# Solenoid_Driver_x8.net
KiCad netlist of a schematic drawn in EAGLE
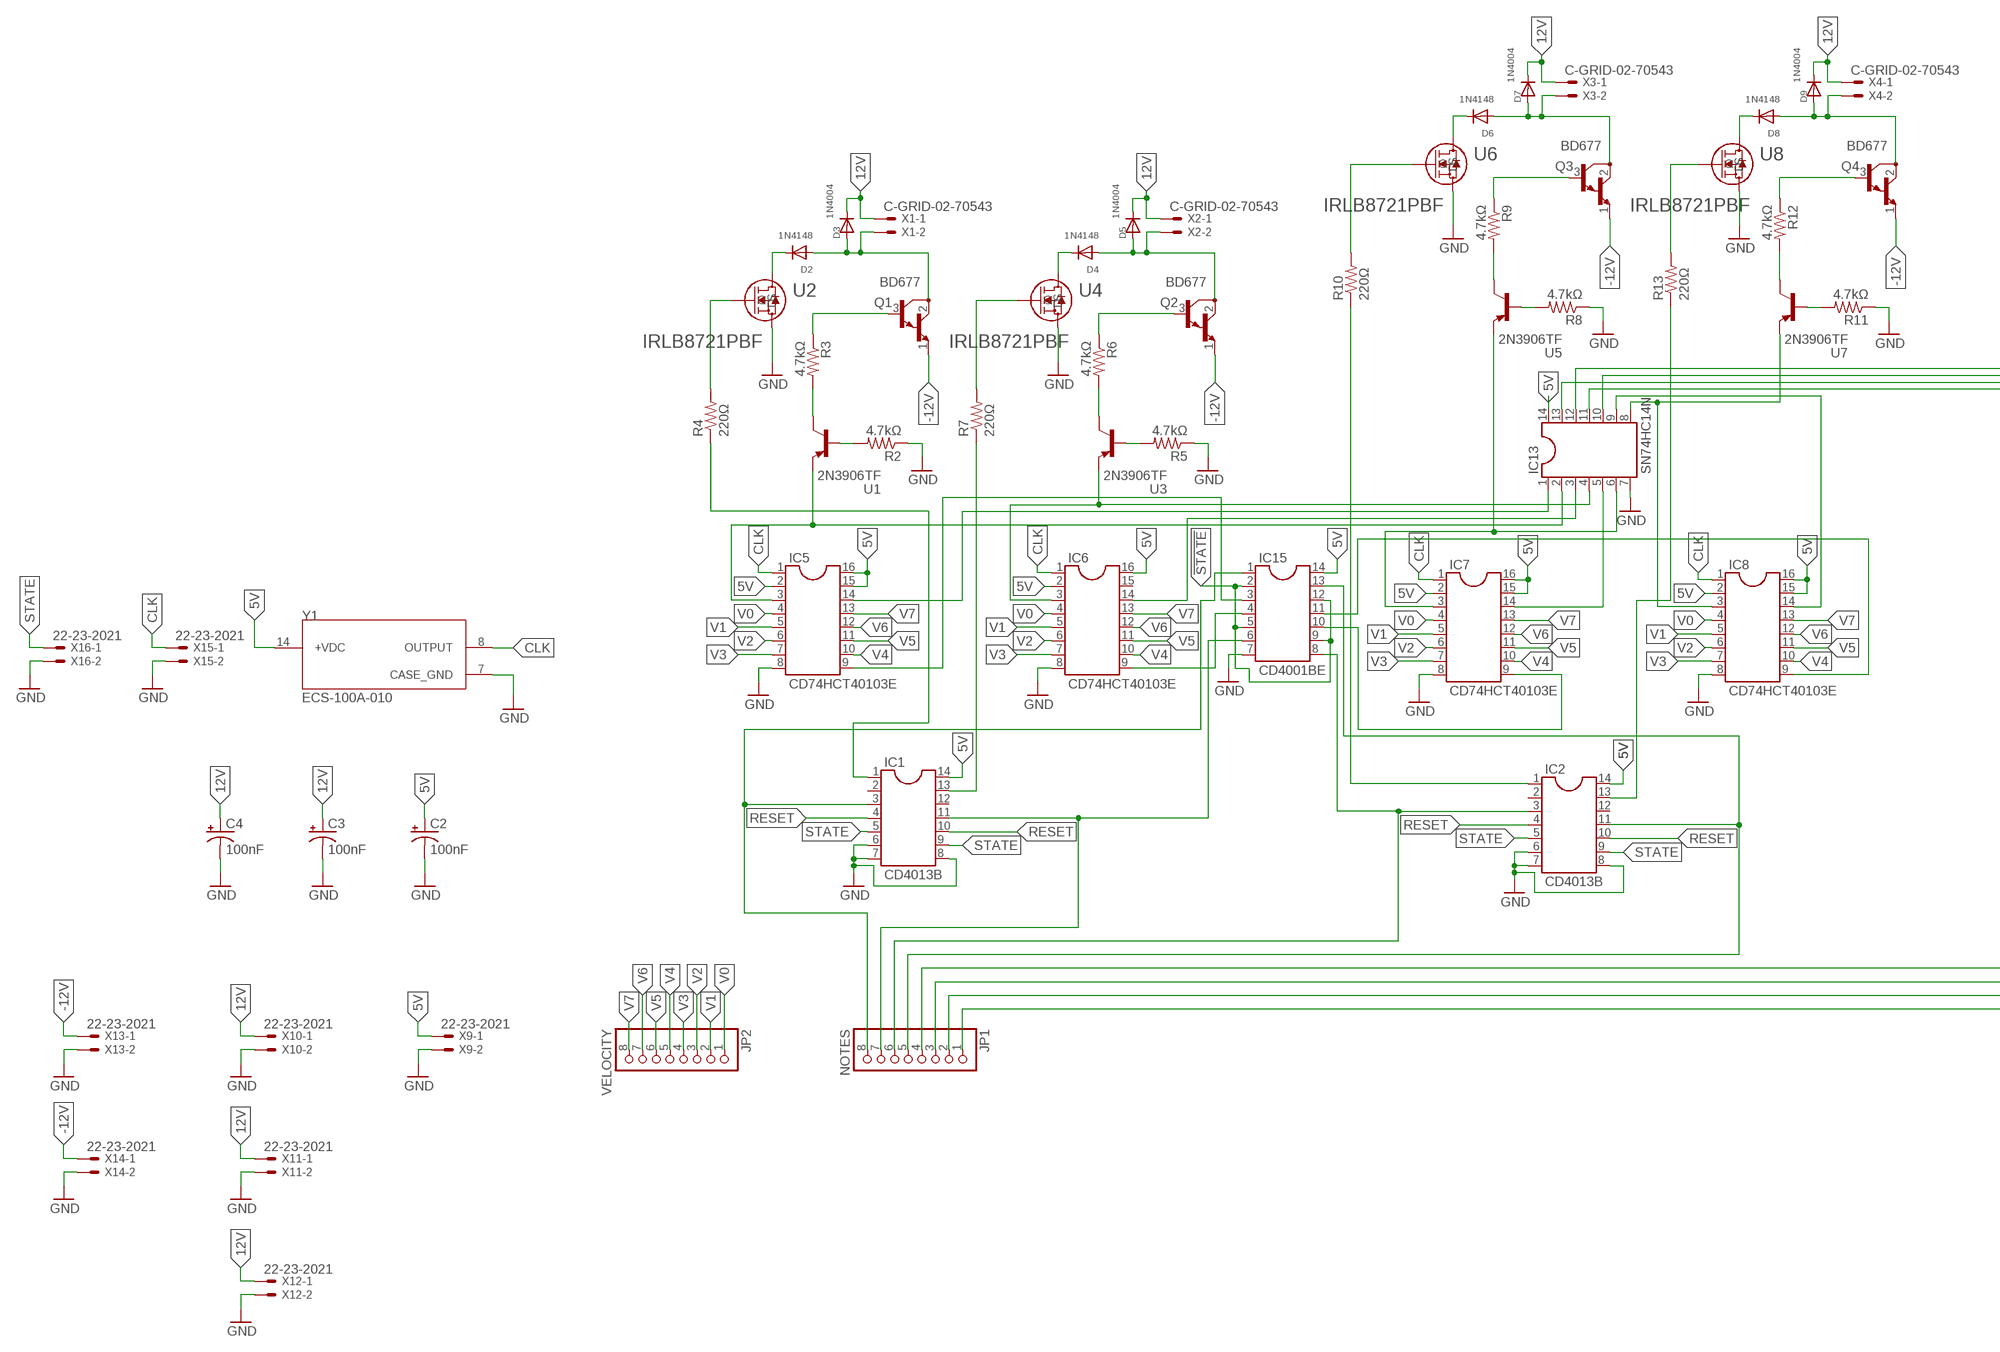
[diagram p0: schematic, sheet 1, part 1 of 2]
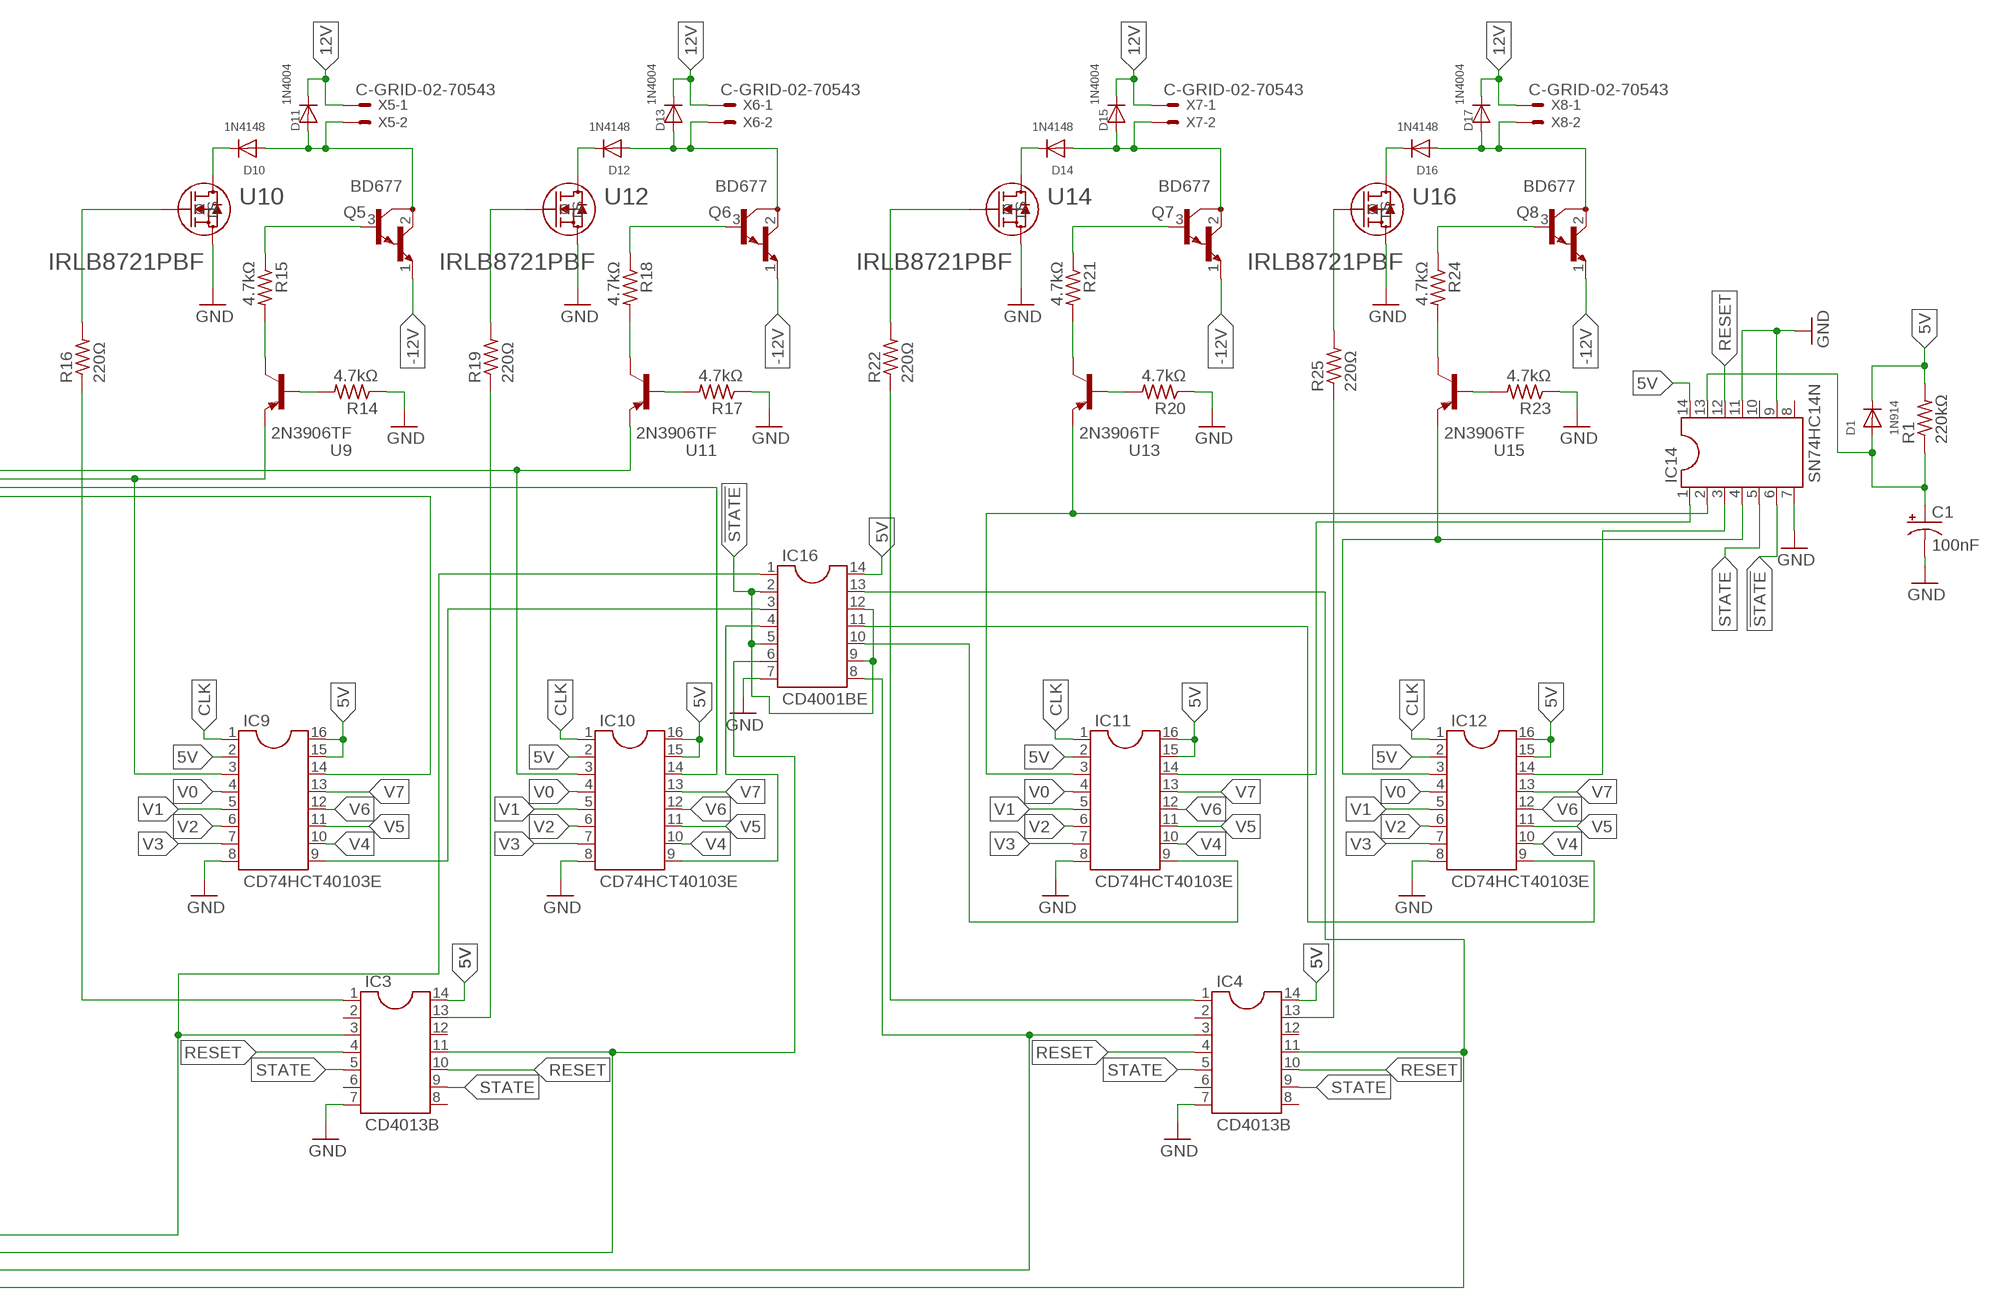
[diagram p1: schematic, sheet 1, part 2 of 2]

(export (version "E")
  (design (tool "Eeschema 10.0.6"))
  (components
    (comp (ref "C1")
      (value "100nF")
      (footprint "eagle-import:E1,8-4")
      (libsource (lib "eagle-import") (part "CPOL-USE1.8-4"))
    )
    (comp (ref "C2")
      (value "100nF")
      (footprint "eagle-import:E1,8-4")
      (libsource (lib "eagle-import") (part "CPOL-USE1.8-4"))
    )
    (comp (ref "C3")
      (value "100nF")
      (footprint "eagle-import:E1,8-4")
      (libsource (lib "eagle-import") (part "CPOL-USE1.8-4"))
    )
    (comp (ref "C4")
      (value "100nF")
      (footprint "eagle-import:E1,8-4")
      (libsource (lib "eagle-import") (part "CPOL-USE1.8-4"))
    )
    (comp (ref "D1")
      (value "1N914")
      (footprint "eagle-import:DO-1N4148")
      (libsource (lib "eagle-import") (part "DIODEDO-1N4148"))
    )
    (comp (ref "D2")
      (value "1N4148")
      (footprint "eagle-import:DO-1N4148")
      (libsource (lib "eagle-import") (part "DIODEDO-1N4148"))
    )
    (comp (ref "D3")
      (value "1N4004")
      (footprint "eagle-import:DO-1N4148")
      (libsource (lib "eagle-import") (part "DIODEDO-1N4148"))
    )
    (comp (ref "D4")
      (value "1N4148")
      (footprint "eagle-import:DO-1N4148")
      (libsource (lib "eagle-import") (part "DIODEDO-1N4148"))
    )
    (comp (ref "D5")
      (value "1N4004")
      (footprint "eagle-import:DO-1N4148")
      (libsource (lib "eagle-import") (part "DIODEDO-1N4148"))
    )
    (comp (ref "D6")
      (value "1N4148")
      (footprint "eagle-import:DO-1N4148")
      (libsource (lib "eagle-import") (part "DIODEDO-1N4148"))
    )
    (comp (ref "D7")
      (value "1N4004")
      (footprint "eagle-import:DO-1N4148")
      (libsource (lib "eagle-import") (part "DIODEDO-1N4148"))
    )
    (comp (ref "D8")
      (value "1N4148")
      (footprint "eagle-import:DO-1N4148")
      (libsource (lib "eagle-import") (part "DIODEDO-1N4148"))
    )
    (comp (ref "D9")
      (value "1N4004")
      (footprint "eagle-import:DO-1N4148")
      (libsource (lib "eagle-import") (part "DIODEDO-1N4148"))
    )
    (comp (ref "D10")
      (value "1N4148")
      (footprint "eagle-import:DO-1N4148")
      (libsource (lib "eagle-import") (part "DIODEDO-1N4148"))
    )
    (comp (ref "D11")
      (value "1N4004")
      (footprint "eagle-import:DO-1N4148")
      (libsource (lib "eagle-import") (part "DIODEDO-1N4148"))
    )
    (comp (ref "D12")
      (value "1N4148")
      (footprint "eagle-import:DO-1N4148")
      (libsource (lib "eagle-import") (part "DIODEDO-1N4148"))
    )
    (comp (ref "D13")
      (value "1N4004")
      (footprint "eagle-import:DO-1N4148")
      (libsource (lib "eagle-import") (part "DIODEDO-1N4148"))
    )
    (comp (ref "D14")
      (value "1N4148")
      (footprint "eagle-import:DO-1N4148")
      (libsource (lib "eagle-import") (part "DIODEDO-1N4148"))
    )
    (comp (ref "D15")
      (value "1N4004")
      (footprint "eagle-import:DO-1N4148")
      (libsource (lib "eagle-import") (part "DIODEDO-1N4148"))
    )
    (comp (ref "D16")
      (value "1N4148")
      (footprint "eagle-import:DO-1N4148")
      (libsource (lib "eagle-import") (part "DIODEDO-1N4148"))
    )
    (comp (ref "D17")
      (value "1N4004")
      (footprint "eagle-import:DO-1N4148")
      (libsource (lib "eagle-import") (part "DIODEDO-1N4148"))
    )
    (comp (ref "IC1")
      (value "CD4013B")
      (footprint "eagle-import:SOCKET-14")
      (libsource (lib "eagle-import") (part "DIL14S"))
    )
    (comp (ref "IC2")
      (value "CD4013B")
      (footprint "eagle-import:SOCKET-14")
      (libsource (lib "eagle-import") (part "DIL14S"))
    )
    (comp (ref "IC3")
      (value "CD4013B")
      (footprint "eagle-import:SOCKET-14")
      (libsource (lib "eagle-import") (part "DIL14S"))
    )
    (comp (ref "IC4")
      (value "CD4013B")
      (footprint "eagle-import:SOCKET-14")
      (libsource (lib "eagle-import") (part "DIL14S"))
    )
    (comp (ref "IC5")
      (value "CD74HCT40103E")
      (footprint "eagle-import:SOCKET-16")
      (libsource (lib "eagle-import") (part "DIL16S"))
    )
    (comp (ref "IC6")
      (value "CD74HCT40103E")
      (footprint "eagle-import:SOCKET-16")
      (libsource (lib "eagle-import") (part "DIL16S"))
    )
    (comp (ref "IC7")
      (value "CD74HCT40103E")
      (footprint "eagle-import:SOCKET-16")
      (libsource (lib "eagle-import") (part "DIL16S"))
    )
    (comp (ref "IC8")
      (value "CD74HCT40103E")
      (footprint "eagle-import:SOCKET-16")
      (libsource (lib "eagle-import") (part "DIL16S"))
    )
    (comp (ref "IC9")
      (value "CD74HCT40103E")
      (footprint "eagle-import:SOCKET-16")
      (libsource (lib "eagle-import") (part "DIL16S"))
    )
    (comp (ref "IC10")
      (value "CD74HCT40103E")
      (footprint "eagle-import:SOCKET-16")
      (libsource (lib "eagle-import") (part "DIL16S"))
    )
    (comp (ref "IC11")
      (value "CD74HCT40103E")
      (footprint "eagle-import:SOCKET-16")
      (libsource (lib "eagle-import") (part "DIL16S"))
    )
    (comp (ref "IC12")
      (value "CD74HCT40103E")
      (footprint "eagle-import:SOCKET-16")
      (libsource (lib "eagle-import") (part "DIL16S"))
    )
    (comp (ref "IC13")
      (value "SN74HC14N")
      (footprint "eagle-import:SOCKET-14")
      (libsource (lib "eagle-import") (part "DIL14S"))
    )
    (comp (ref "IC14")
      (value "SN74HC14N")
      (footprint "eagle-import:SOCKET-14")
      (libsource (lib "eagle-import") (part "DIL14S"))
    )
    (comp (ref "IC15")
      (value "CD4001BE")
      (footprint "eagle-import:SOCKET-14")
      (libsource (lib "eagle-import") (part "DIL14S"))
    )
    (comp (ref "IC16")
      (value "CD4001BE")
      (footprint "eagle-import:SOCKET-14")
      (libsource (lib "eagle-import") (part "DIL14S"))
    )
    (comp (ref "JP1")
      (value "NOTES")
      (footprint "eagle-import:1X08-BIG")
      (libsource (lib "eagle-import") (part "PINHD-1X8BIG"))
    )
    (comp (ref "JP2")
      (value "VELOCITY")
      (footprint "eagle-import:1X08-BIG")
      (libsource (lib "eagle-import") (part "PINHD-1X8BIG"))
    )
    (comp (ref "Q1")
      (value "BD677")
      (footprint "eagle-import:TO126")
      (libsource (lib "eagle-import") (part "BD677"))
    )
    (comp (ref "Q2")
      (value "BD677")
      (footprint "eagle-import:TO126")
      (libsource (lib "eagle-import") (part "BD677"))
    )
    (comp (ref "Q3")
      (value "BD677")
      (footprint "eagle-import:TO126")
      (libsource (lib "eagle-import") (part "BD677"))
    )
    (comp (ref "Q4")
      (value "BD677")
      (footprint "eagle-import:TO126")
      (libsource (lib "eagle-import") (part "BD677"))
    )
    (comp (ref "Q5")
      (value "BD677")
      (footprint "eagle-import:TO126")
      (libsource (lib "eagle-import") (part "BD677"))
    )
    (comp (ref "Q6")
      (value "BD677")
      (footprint "eagle-import:TO126")
      (libsource (lib "eagle-import") (part "BD677"))
    )
    (comp (ref "Q7")
      (value "BD677")
      (footprint "eagle-import:TO126")
      (libsource (lib "eagle-import") (part "BD677"))
    )
    (comp (ref "Q8")
      (value "BD677")
      (footprint "eagle-import:TO126")
      (libsource (lib "eagle-import") (part "BD677"))
    )
    (comp (ref "R1")
      (value "220kΩ")
      (footprint "eagle-import:0207_10")
      (libsource (lib "eagle-import") (part "R-US_0207/10"))
    )
    (comp (ref "R2")
      (value "4.7kΩ")
      (footprint "eagle-import:0207_10")
      (libsource (lib "eagle-import") (part "R-US_0207/10"))
    )
    (comp (ref "R3")
      (value "4.7kΩ")
      (footprint "eagle-import:0207_10")
      (libsource (lib "eagle-import") (part "R-US_0207/10"))
    )
    (comp (ref "R4")
      (value "220Ω")
      (footprint "eagle-import:0207_10")
      (libsource (lib "eagle-import") (part "R-US_0207/10"))
    )
    (comp (ref "R5")
      (value "4.7kΩ")
      (footprint "eagle-import:0207_10")
      (libsource (lib "eagle-import") (part "R-US_0207/10"))
    )
    (comp (ref "R6")
      (value "4.7kΩ")
      (footprint "eagle-import:0207_10")
      (libsource (lib "eagle-import") (part "R-US_0207/10"))
    )
    (comp (ref "R7")
      (value "220Ω")
      (footprint "eagle-import:0207_10")
      (libsource (lib "eagle-import") (part "R-US_0207/10"))
    )
    (comp (ref "R8")
      (value "4.7kΩ")
      (footprint "eagle-import:0207_10")
      (libsource (lib "eagle-import") (part "R-US_0207/10"))
    )
    (comp (ref "R9")
      (value "4.7kΩ")
      (footprint "eagle-import:0207_10")
      (libsource (lib "eagle-import") (part "R-US_0207/10"))
    )
    (comp (ref "R10")
      (value "220Ω")
      (footprint "eagle-import:0207_10")
      (libsource (lib "eagle-import") (part "R-US_0207/10"))
    )
    (comp (ref "R11")
      (value "4.7kΩ")
      (footprint "eagle-import:0207_10")
      (libsource (lib "eagle-import") (part "R-US_0207/10"))
    )
    (comp (ref "R12")
      (value "4.7kΩ")
      (footprint "eagle-import:0207_10")
      (libsource (lib "eagle-import") (part "R-US_0207/10"))
    )
    (comp (ref "R13")
      (value "220Ω")
      (footprint "eagle-import:0207_10")
      (libsource (lib "eagle-import") (part "R-US_0207/10"))
    )
    (comp (ref "R14")
      (value "4.7kΩ")
      (footprint "eagle-import:0207_10")
      (libsource (lib "eagle-import") (part "R-US_0207/10"))
    )
    (comp (ref "R15")
      (value "4.7kΩ")
      (footprint "eagle-import:0207_10")
      (libsource (lib "eagle-import") (part "R-US_0207/10"))
    )
    (comp (ref "R16")
      (value "220Ω")
      (footprint "eagle-import:0207_10")
      (libsource (lib "eagle-import") (part "R-US_0207/10"))
    )
    (comp (ref "R17")
      (value "4.7kΩ")
      (footprint "eagle-import:0207_10")
      (libsource (lib "eagle-import") (part "R-US_0207/10"))
    )
    (comp (ref "R18")
      (value "4.7kΩ")
      (footprint "eagle-import:0207_10")
      (libsource (lib "eagle-import") (part "R-US_0207/10"))
    )
    (comp (ref "R19")
      (value "220Ω")
      (footprint "eagle-import:0207_10")
      (libsource (lib "eagle-import") (part "R-US_0207/10"))
    )
    (comp (ref "R20")
      (value "4.7kΩ")
      (footprint "eagle-import:0207_10")
      (libsource (lib "eagle-import") (part "R-US_0207/10"))
    )
    (comp (ref "R21")
      (value "4.7kΩ")
      (footprint "eagle-import:0207_10")
      (libsource (lib "eagle-import") (part "R-US_0207/10"))
    )
    (comp (ref "R22")
      (value "220Ω")
      (footprint "eagle-import:0207_10")
      (libsource (lib "eagle-import") (part "R-US_0207/10"))
    )
    (comp (ref "R23")
      (value "4.7kΩ")
      (footprint "eagle-import:0207_10")
      (libsource (lib "eagle-import") (part "R-US_0207/10"))
    )
    (comp (ref "R24")
      (value "4.7kΩ")
      (footprint "eagle-import:0207_10")
      (libsource (lib "eagle-import") (part "R-US_0207/10"))
    )
    (comp (ref "R25")
      (value "220Ω")
      (footprint "eagle-import:0207_10")
      (libsource (lib "eagle-import") (part "R-US_0207/10"))
    )
    (comp (ref "U1")
      (value "2N3906TF")
      (footprint "eagle-import:TO-92-3L_5P33X5P2_ONS")
      (fields (field (name "COPYRIGHT") "Copyright (C) 2024 Ultra Librarian. All rights reserved."))
      (libsource (lib "eagle-import") (part "2N3906TF"))
    )
    (comp (ref "U2")
      (value "IRLB8721PBF")
      (footprint "eagle-import:PG-TO220-3_INF")
      (fields (field (name "COPYRIGHT") "Copyright (C) 2024 Ultra Librarian. All rights reserved."))
      (libsource (lib "eagle-import") (part "IRLB8721PBF"))
    )
    (comp (ref "U3")
      (value "2N3906TF")
      (footprint "eagle-import:TO-92-3L_5P33X5P2_ONS")
      (fields (field (name "COPYRIGHT") "Copyright (C) 2024 Ultra Librarian. All rights reserved."))
      (libsource (lib "eagle-import") (part "2N3906TF"))
    )
    (comp (ref "U4")
      (value "IRLB8721PBF")
      (footprint "eagle-import:PG-TO220-3_INF")
      (fields (field (name "COPYRIGHT") "Copyright (C) 2024 Ultra Librarian. All rights reserved."))
      (libsource (lib "eagle-import") (part "IRLB8721PBF"))
    )
    (comp (ref "U5")
      (value "2N3906TF")
      (footprint "eagle-import:TO-92-3L_5P33X5P2_ONS")
      (fields (field (name "COPYRIGHT") "Copyright (C) 2024 Ultra Librarian. All rights reserved."))
      (libsource (lib "eagle-import") (part "2N3906TF"))
    )
    (comp (ref "U6")
      (value "IRLB8721PBF")
      (footprint "eagle-import:PG-TO220-3_INF")
      (fields (field (name "COPYRIGHT") "Copyright (C) 2024 Ultra Librarian. All rights reserved."))
      (libsource (lib "eagle-import") (part "IRLB8721PBF"))
    )
    (comp (ref "U7")
      (value "2N3906TF")
      (footprint "eagle-import:TO-92-3L_5P33X5P2_ONS")
      (fields (field (name "COPYRIGHT") "Copyright (C) 2024 Ultra Librarian. All rights reserved."))
      (libsource (lib "eagle-import") (part "2N3906TF"))
    )
    (comp (ref "U8")
      (value "IRLB8721PBF")
      (footprint "eagle-import:PG-TO220-3_INF")
      (fields (field (name "COPYRIGHT") "Copyright (C) 2024 Ultra Librarian. All rights reserved."))
      (libsource (lib "eagle-import") (part "IRLB8721PBF"))
    )
    (comp (ref "U9")
      (value "2N3906TF")
      (footprint "eagle-import:TO-92-3L_5P33X5P2_ONS")
      (fields (field (name "COPYRIGHT") "Copyright (C) 2024 Ultra Librarian. All rights reserved."))
      (libsource (lib "eagle-import") (part "2N3906TF"))
    )
    (comp (ref "U10")
      (value "IRLB8721PBF")
      (footprint "eagle-import:PG-TO220-3_INF")
      (fields (field (name "COPYRIGHT") "Copyright (C) 2024 Ultra Librarian. All rights reserved."))
      (libsource (lib "eagle-import") (part "IRLB8721PBF"))
    )
    (comp (ref "U11")
      (value "2N3906TF")
      (footprint "eagle-import:TO-92-3L_5P33X5P2_ONS")
      (fields (field (name "COPYRIGHT") "Copyright (C) 2024 Ultra Librarian. All rights reserved."))
      (libsource (lib "eagle-import") (part "2N3906TF"))
    )
    (comp (ref "U12")
      (value "IRLB8721PBF")
      (footprint "eagle-import:PG-TO220-3_INF")
      (fields (field (name "COPYRIGHT") "Copyright (C) 2024 Ultra Librarian. All rights reserved."))
      (libsource (lib "eagle-import") (part "IRLB8721PBF"))
    )
    (comp (ref "U13")
      (value "2N3906TF")
      (footprint "eagle-import:TO-92-3L_5P33X5P2_ONS")
      (fields (field (name "COPYRIGHT") "Copyright (C) 2024 Ultra Librarian. All rights reserved."))
      (libsource (lib "eagle-import") (part "2N3906TF"))
    )
    (comp (ref "U14")
      (value "IRLB8721PBF")
      (footprint "eagle-import:PG-TO220-3_INF")
      (fields (field (name "COPYRIGHT") "Copyright (C) 2024 Ultra Librarian. All rights reserved."))
      (libsource (lib "eagle-import") (part "IRLB8721PBF"))
    )
    (comp (ref "U15")
      (value "2N3906TF")
      (footprint "eagle-import:TO-92-3L_5P33X5P2_ONS")
      (fields (field (name "COPYRIGHT") "Copyright (C) 2024 Ultra Librarian. All rights reserved."))
      (libsource (lib "eagle-import") (part "2N3906TF"))
    )
    (comp (ref "U16")
      (value "IRLB8721PBF")
      (footprint "eagle-import:PG-TO220-3_INF")
      (fields (field (name "COPYRIGHT") "Copyright (C) 2024 Ultra Librarian. All rights reserved."))
      (libsource (lib "eagle-import") (part "IRLB8721PBF"))
    )
    (comp (ref "X1")
      (value "C-GRID-02-70543")
      (footprint "eagle-import:70543-02")
      (fields (field (name "MF") "MOLEX"))
      (libsource (lib "eagle-import") (part "C-GRID-02-70543"))
    )
    (comp (ref "X2")
      (value "C-GRID-02-70543")
      (footprint "eagle-import:70543-02")
      (fields (field (name "MF") "MOLEX"))
      (libsource (lib "eagle-import") (part "C-GRID-02-70543"))
    )
    (comp (ref "X3")
      (value "C-GRID-02-70543")
      (footprint "eagle-import:70543-02")
      (fields (field (name "MF") "MOLEX"))
      (libsource (lib "eagle-import") (part "C-GRID-02-70543"))
    )
    (comp (ref "X4")
      (value "C-GRID-02-70543")
      (footprint "eagle-import:70543-02")
      (fields (field (name "MF") "MOLEX"))
      (libsource (lib "eagle-import") (part "C-GRID-02-70543"))
    )
    (comp (ref "X5")
      (value "C-GRID-02-70543")
      (footprint "eagle-import:70543-02")
      (fields (field (name "MF") "MOLEX"))
      (libsource (lib "eagle-import") (part "C-GRID-02-70543"))
    )
    (comp (ref "X6")
      (value "C-GRID-02-70543")
      (footprint "eagle-import:70543-02")
      (fields (field (name "MF") "MOLEX"))
      (libsource (lib "eagle-import") (part "C-GRID-02-70543"))
    )
    (comp (ref "X7")
      (value "C-GRID-02-70543")
      (footprint "eagle-import:70543-02")
      (fields (field (name "MF") "MOLEX"))
      (libsource (lib "eagle-import") (part "C-GRID-02-70543"))
    )
    (comp (ref "X8")
      (value "C-GRID-02-70543")
      (footprint "eagle-import:70543-02")
      (fields (field (name "MF") "MOLEX"))
      (libsource (lib "eagle-import") (part "C-GRID-02-70543"))
    )
    (comp (ref "X9")
      (value "22-23-2021")
      (footprint "eagle-import:22-23-2021")
      (fields (field (name "MF") "MOLEX"))
      (libsource (lib "eagle-import") (part "22-23-2021"))
    )
    (comp (ref "X10")
      (value "22-23-2021")
      (footprint "eagle-import:22-23-2021")
      (fields (field (name "MF") "MOLEX"))
      (libsource (lib "eagle-import") (part "22-23-2021"))
    )
    (comp (ref "X11")
      (value "22-23-2021")
      (footprint "eagle-import:22-23-2021")
      (fields (field (name "MF") "MOLEX"))
      (libsource (lib "eagle-import") (part "22-23-2021"))
    )
    (comp (ref "X12")
      (value "22-23-2021")
      (footprint "eagle-import:22-23-2021")
      (fields (field (name "MF") "MOLEX"))
      (libsource (lib "eagle-import") (part "22-23-2021"))
    )
    (comp (ref "X13")
      (value "22-23-2021")
      (footprint "eagle-import:22-23-2021")
      (fields (field (name "MF") "MOLEX"))
      (libsource (lib "eagle-import") (part "22-23-2021"))
    )
    (comp (ref "X14")
      (value "22-23-2021")
      (footprint "eagle-import:22-23-2021")
      (fields (field (name "MF") "MOLEX"))
      (libsource (lib "eagle-import") (part "22-23-2021"))
    )
    (comp (ref "X15")
      (value "22-23-2021")
      (footprint "eagle-import:22-23-2021")
      (fields (field (name "MF") "MOLEX"))
      (libsource (lib "eagle-import") (part "22-23-2021"))
    )
    (comp (ref "X16")
      (value "22-23-2021")
      (footprint "eagle-import:22-23-2021")
      (fields (field (name "MF") "MOLEX"))
      (libsource (lib "eagle-import") (part "22-23-2021"))
    )
    (comp (ref "Y1")
      (value "ECS-100A-010")
      (footprint "eagle-import:OSC_ECS-100A-010")
      (fields (field (name "MANUFACTURER") "ECS Inc."))
      (libsource (lib "eagle-import") (part "ECS-100A-010"))
    )
  )
  (nets
    (net (code "1") (name "-12V") (class "Default")
      (node (ref "Q1") (pin "1") (pinfunction "E_1") (pintype "passive"))
      (node (ref "Q2") (pin "1") (pinfunction "E_1") (pintype "passive"))
      (node (ref "Q3") (pin "1") (pinfunction "E_1") (pintype "passive"))
      (node (ref "Q4") (pin "1") (pinfunction "E_1") (pintype "passive"))
      (node (ref "Q5") (pin "1") (pinfunction "E_1") (pintype "passive"))
      (node (ref "Q6") (pin "1") (pinfunction "E_1") (pintype "passive"))
      (node (ref "Q7") (pin "1") (pinfunction "E_1") (pintype "passive"))
      (node (ref "Q8") (pin "1") (pinfunction "E_1") (pintype "passive"))
      (node (ref "X13") (pin "1") (pinfunction "S_1") (pintype "passive"))
      (node (ref "X14") (pin "1") (pinfunction "S_1") (pintype "passive"))
    )
    (net (code "2") (name "/~{STATE}") (class "Default")
      (node (ref "IC14") (pin "6") (pinfunction "6_6") (pintype "passive"))
      (node (ref "IC15") (pin "12") (pinfunction "12_12") (pintype "passive"))
      (node (ref "IC15") (pin "2") (pinfunction "2_2") (pintype "passive"))
      (node (ref "IC15") (pin "5") (pinfunction "5_5") (pintype "passive"))
      (node (ref "IC15") (pin "9") (pinfunction "9_9") (pintype "passive"))
      (node (ref "IC16") (pin "12") (pinfunction "12_12") (pintype "passive"))
      (node (ref "IC16") (pin "2") (pinfunction "2_2") (pintype "passive"))
      (node (ref "IC16") (pin "5") (pinfunction "5_5") (pintype "passive"))
      (node (ref "IC16") (pin "9") (pinfunction "9_9") (pintype "passive"))
    )
    (net (code "3") (name "5V") (class "Default")
      (node (ref "C2") (pin "+") (pinfunction "+_+") (pintype "passive"))
      (node (ref "D1") (pin "C") (pinfunction "C_C") (pintype "passive"))
      (node (ref "IC1") (pin "14") (pinfunction "14_14") (pintype "passive"))
      (node (ref "IC10") (pin "15") (pinfunction "15_15") (pintype "passive"))
      (node (ref "IC10") (pin "16") (pinfunction "16_16") (pintype "passive"))
      (node (ref "IC10") (pin "2") (pinfunction "2_2") (pintype "passive"))
      (node (ref "IC11") (pin "15") (pinfunction "15_15") (pintype "passive"))
      (node (ref "IC11") (pin "16") (pinfunction "16_16") (pintype "passive"))
      (node (ref "IC11") (pin "2") (pinfunction "2_2") (pintype "passive"))
      (node (ref "IC12") (pin "15") (pinfunction "15_15") (pintype "passive"))
      (node (ref "IC12") (pin "16") (pinfunction "16_16") (pintype "passive"))
      (node (ref "IC12") (pin "2") (pinfunction "2_2") (pintype "passive"))
      (node (ref "IC13") (pin "14") (pinfunction "14_14") (pintype "passive"))
      (node (ref "IC14") (pin "14") (pinfunction "14_14") (pintype "passive"))
      (node (ref "IC15") (pin "14") (pinfunction "14_14") (pintype "passive"))
      (node (ref "IC16") (pin "14") (pinfunction "14_14") (pintype "passive"))
      (node (ref "IC2") (pin "14") (pinfunction "14_14") (pintype "passive"))
      (node (ref "IC3") (pin "14") (pinfunction "14_14") (pintype "passive"))
      (node (ref "IC4") (pin "14") (pinfunction "14_14") (pintype "passive"))
      (node (ref "IC5") (pin "15") (pinfunction "15_15") (pintype "passive"))
      (node (ref "IC5") (pin "16") (pinfunction "16_16") (pintype "passive"))
      (node (ref "IC5") (pin "2") (pinfunction "2_2") (pintype "passive"))
      (node (ref "IC6") (pin "16") (pinfunction "16_16") (pintype "passive"))
      (node (ref "IC6") (pin "2") (pinfunction "2_2") (pintype "passive"))
      (node (ref "IC7") (pin "15") (pinfunction "15_15") (pintype "passive"))
      (node (ref "IC7") (pin "16") (pinfunction "16_16") (pintype "passive"))
      (node (ref "IC7") (pin "2") (pinfunction "2_2") (pintype "passive"))
      (node (ref "IC8") (pin "15") (pinfunction "15_15") (pintype "passive"))
      (node (ref "IC8") (pin "16") (pinfunction "16_16") (pintype "passive"))
      (node (ref "IC8") (pin "2") (pinfunction "2_2") (pintype "passive"))
      (node (ref "IC9") (pin "15") (pinfunction "15_15") (pintype "passive"))
      (node (ref "IC9") (pin "16") (pinfunction "16_16") (pintype "passive"))
      (node (ref "IC9") (pin "2") (pinfunction "2_2") (pintype "passive"))
      (node (ref "R1") (pin "2") (pinfunction "2_2") (pintype "passive"))
      (node (ref "X9") (pin "1") (pinfunction "S_1") (pintype "passive"))
      (node (ref "Y1") (pin "14") (pinfunction "+VDC_14") (pintype "input"))
    )
    (net (code "4") (name "12V") (class "Default")
      (node (ref "C3") (pin "+") (pinfunction "+_+") (pintype "passive"))
      (node (ref "C4") (pin "+") (pinfunction "+_+") (pintype "passive"))
      (node (ref "D11") (pin "C") (pinfunction "C_C") (pintype "passive"))
      (node (ref "D13") (pin "C") (pinfunction "C_C") (pintype "passive"))
      (node (ref "D15") (pin "C") (pinfunction "C_C") (pintype "passive"))
      (node (ref "D17") (pin "C") (pinfunction "C_C") (pintype "passive"))
      (node (ref "D3") (pin "C") (pinfunction "C_C") (pintype "passive"))
      (node (ref "D5") (pin "C") (pinfunction "C_C") (pintype "passive"))
      (node (ref "D7") (pin "C") (pinfunction "C_C") (pintype "passive"))
      (node (ref "D9") (pin "C") (pinfunction "C_C") (pintype "passive"))
      (node (ref "X1") (pin "1") (pinfunction "S_1") (pintype "passive"))
      (node (ref "X10") (pin "1") (pinfunction "S_1") (pintype "passive"))
      (node (ref "X11") (pin "1") (pinfunction "S_1") (pintype "passive"))
      (node (ref "X12") (pin "1") (pinfunction "S_1") (pintype "passive"))
      (node (ref "X2") (pin "1") (pinfunction "S_1") (pintype "passive"))
      (node (ref "X3") (pin "1") (pinfunction "S_1") (pintype "passive"))
      (node (ref "X4") (pin "1") (pinfunction "S_1") (pintype "passive"))
      (node (ref "X5") (pin "1") (pinfunction "S_1") (pintype "passive"))
      (node (ref "X6") (pin "1") (pinfunction "S_1") (pintype "passive"))
      (node (ref "X7") (pin "1") (pinfunction "S_1") (pintype "passive"))
      (node (ref "X8") (pin "1") (pinfunction "S_1") (pintype "passive"))
    )
    (net (code "5") (name "CLK") (class "Default")
      (node (ref "IC10") (pin "1") (pinfunction "1_1") (pintype "passive"))
      (node (ref "IC11") (pin "1") (pinfunction "1_1") (pintype "passive"))
      (node (ref "IC12") (pin "1") (pinfunction "1_1") (pintype "passive"))
      (node (ref "IC5") (pin "1") (pinfunction "1_1") (pintype "passive"))
      (node (ref "IC6") (pin "1") (pinfunction "1_1") (pintype "passive"))
      (node (ref "IC7") (pin "1") (pinfunction "1_1") (pintype "passive"))
      (node (ref "IC8") (pin "1") (pinfunction "1_1") (pintype "passive"))
      (node (ref "IC9") (pin "1") (pinfunction "1_1") (pintype "passive"))
      (node (ref "X15") (pin "1") (pinfunction "S_1") (pintype "passive"))
      (node (ref "Y1") (pin "8") (pinfunction "OUTPUT_8") (pintype "output"))
    )
    (net (code "6") (name "GND") (class "Default")
      (node (ref "C1") (pin "-") (pinfunction "-_-") (pintype "passive"))
      (node (ref "C2") (pin "-") (pinfunction "-_-") (pintype "passive"))
      (node (ref "C3") (pin "-") (pinfunction "-_-") (pintype "passive"))
      (node (ref "C4") (pin "-") (pinfunction "-_-") (pintype "passive"))
      (node (ref "IC1") (pin "6") (pinfunction "6_6") (pintype "passive"))
      (node (ref "IC1") (pin "7") (pinfunction "7_7") (pintype "passive"))
      (node (ref "IC1") (pin "8") (pinfunction "8_8") (pintype "passive"))
      (node (ref "IC10") (pin "8") (pinfunction "8_8") (pintype "passive"))
      (node (ref "IC11") (pin "8") (pinfunction "8_8") (pintype "passive"))
      (node (ref "IC12") (pin "8") (pinfunction "8_8") (pintype "passive"))
      (node (ref "IC13") (pin "7") (pinfunction "7_7") (pintype "passive"))
      (node (ref "IC14") (pin "11") (pinfunction "11_11") (pintype "passive"))
      (node (ref "IC14") (pin "7") (pinfunction "7_7") (pintype "passive"))
      (node (ref "IC14") (pin "9") (pinfunction "9_9") (pintype "passive"))
      (node (ref "IC15") (pin "7") (pinfunction "7_7") (pintype "passive"))
      (node (ref "IC16") (pin "7") (pinfunction "7_7") (pintype "passive"))
      (node (ref "IC2") (pin "6") (pinfunction "6_6") (pintype "passive"))
      (node (ref "IC2") (pin "7") (pinfunction "7_7") (pintype "passive"))
      (node (ref "IC2") (pin "8") (pinfunction "8_8") (pintype "passive"))
      (node (ref "IC3") (pin "7") (pinfunction "7_7") (pintype "passive"))
      (node (ref "IC4") (pin "7") (pinfunction "7_7") (pintype "passive"))
      (node (ref "IC5") (pin "8") (pinfunction "8_8") (pintype "passive"))
      (node (ref "IC6") (pin "8") (pinfunction "8_8") (pintype "passive"))
      (node (ref "IC7") (pin "8") (pinfunction "8_8") (pintype "passive"))
      (node (ref "IC8") (pin "8") (pinfunction "8_8") (pintype "passive"))
      (node (ref "IC9") (pin "8") (pinfunction "8_8") (pintype "passive"))
      (node (ref "R11") (pin "1") (pinfunction "1_1") (pintype "passive"))
      (node (ref "R14") (pin "1") (pinfunction "1_1") (pintype "passive"))
      (node (ref "R17") (pin "1") (pinfunction "1_1") (pintype "passive"))
      (node (ref "R2") (pin "1") (pinfunction "1_1") (pintype "passive"))
      (node (ref "R20") (pin "1") (pinfunction "1_1") (pintype "passive"))
      (node (ref "R23") (pin "1") (pinfunction "1_1") (pintype "passive"))
      (node (ref "R5") (pin "1") (pinfunction "1_1") (pintype "passive"))
      (node (ref "R8") (pin "1") (pinfunction "1_1") (pintype "passive"))
      (node (ref "U10") (pin "3") (pinfunction "S_3") (pintype "passive"))
      (node (ref "U12") (pin "3") (pinfunction "S_3") (pintype "passive"))
      (node (ref "U14") (pin "3") (pinfunction "S_3") (pintype "passive"))
      (node (ref "U16") (pin "3") (pinfunction "S_3") (pintype "passive"))
      (node (ref "U2") (pin "3") (pinfunction "S_3") (pintype "passive"))
      (node (ref "U4") (pin "3") (pinfunction "S_3") (pintype "passive"))
      (node (ref "U6") (pin "3") (pinfunction "S_3") (pintype "passive"))
      (node (ref "U8") (pin "3") (pinfunction "S_3") (pintype "passive"))
      (node (ref "X10") (pin "2") (pinfunction "S_2") (pintype "passive"))
      (node (ref "X11") (pin "2") (pinfunction "S_2") (pintype "passive"))
      (node (ref "X12") (pin "2") (pinfunction "S_2") (pintype "passive"))
      (node (ref "X13") (pin "2") (pinfunction "S_2") (pintype "passive"))
      (node (ref "X14") (pin "2") (pinfunction "S_2") (pintype "passive"))
      (node (ref "X15") (pin "2") (pinfunction "S_2") (pintype "passive"))
      (node (ref "X16") (pin "2") (pinfunction "S_2") (pintype "passive"))
      (node (ref "X9") (pin "2") (pinfunction "S_2") (pintype "passive"))
      (node (ref "Y1") (pin "7") (pinfunction "CASE_GND_7") (pintype "power_in"))
    )
    (net (code "7") (name "Net-(C1-Pad+)") (class "Default")
      (node (ref "C1") (pin "+") (pinfunction "+_+") (pintype "passive"))
      (node (ref "D1") (pin "A") (pinfunction "A_A") (pintype "passive"))
      (node (ref "IC14") (pin "13") (pinfunction "13_13") (pintype "passive"))
      (node (ref "R1") (pin "1") (pinfunction "1_1") (pintype "passive"))
    )
    (net (code "8") (name "Net-(IC1-Pad1)") (class "Default")
      (node (ref "IC1") (pin "1") (pinfunction "1_1") (pintype "passive"))
      (node (ref "R4") (pin "1") (pinfunction "1_1") (pintype "passive"))
    )
    (net (code "9") (name "Net-(IC1-Pad3)") (class "Default")
      (node (ref "IC1") (pin "3") (pinfunction "3_3") (pintype "passive"))
      (node (ref "IC15") (pin "1") (pinfunction "1_1") (pintype "passive"))
      (node (ref "JP1") (pin "8") (pinfunction "8_8") (pintype "passive"))
    )
    (net (code "10") (name "Net-(IC1-Pad11)") (class "Default")
      (node (ref "IC1") (pin "11") (pinfunction "11_11") (pintype "passive"))
      (node (ref "IC15") (pin "6") (pinfunction "6_6") (pintype "passive"))
      (node (ref "JP1") (pin "7") (pinfunction "7_7") (pintype "passive"))
    )
    (net (code "11") (name "Net-(IC1-Pad13)") (class "Default")
      (node (ref "IC1") (pin "13") (pinfunction "13_13") (pintype "passive"))
      (node (ref "R7") (pin "1") (pinfunction "1_1") (pintype "passive"))
    )
    (net (code "12") (name "Net-(IC2-Pad1)") (class "Default")
      (node (ref "IC2") (pin "1") (pinfunction "1_1") (pintype "passive"))
      (node (ref "R10") (pin "1") (pinfunction "1_1") (pintype "passive"))
    )
    (net (code "13") (name "Net-(IC2-Pad13)") (class "Default")
      (node (ref "IC2") (pin "13") (pinfunction "13_13") (pintype "passive"))
      (node (ref "R13") (pin "1") (pinfunction "1_1") (pintype "passive"))
    )
    (net (code "14") (name "Net-(IC3-Pad1)") (class "Default")
      (node (ref "IC3") (pin "1") (pinfunction "1_1") (pintype "passive"))
      (node (ref "R16") (pin "1") (pinfunction "1_1") (pintype "passive"))
    )
    (net (code "15") (name "Net-(IC3-Pad13)") (class "Default")
      (node (ref "IC3") (pin "13") (pinfunction "13_13") (pintype "passive"))
      (node (ref "R19") (pin "1") (pinfunction "1_1") (pintype "passive"))
    )
    (net (code "16") (name "Net-(IC4-Pad1)") (class "Default")
      (node (ref "IC4") (pin "1") (pinfunction "1_1") (pintype "passive"))
      (node (ref "R22") (pin "1") (pinfunction "1_1") (pintype "passive"))
    )
    (net (code "17") (name "Net-(IC4-Pad13)") (class "Default")
      (node (ref "IC4") (pin "13") (pinfunction "13_13") (pintype "passive"))
      (node (ref "R25") (pin "1") (pinfunction "1_1") (pintype "passive"))
    )
    (net (code "18") (name "Net-(IC10-Pad9)") (class "Default")
      (node (ref "IC10") (pin "9") (pinfunction "9_9") (pintype "passive"))
      (node (ref "IC16") (pin "4") (pinfunction "4_4") (pintype "passive"))
    )
    (net (code "19") (name "Net-(IC10-Pad14)") (class "Default")
      (node (ref "IC10") (pin "14") (pinfunction "14_14") (pintype "passive"))
      (node (ref "IC13") (pin "13") (pinfunction "13_13") (pintype "passive"))
    )
    (net (code "20") (name "Net-(IC11-Pad9)") (class "Default")
      (node (ref "IC11") (pin "9") (pinfunction "9_9") (pintype "passive"))
      (node (ref "IC16") (pin "10") (pinfunction "10_10") (pintype "passive"))
    )
    (net (code "21") (name "Net-(IC11-Pad14)") (class "Default")
      (node (ref "IC11") (pin "14") (pinfunction "14_14") (pintype "passive"))
      (node (ref "IC14") (pin "1") (pinfunction "1_1") (pintype "passive"))
    )
    (net (code "22") (name "Net-(IC12-Pad9)") (class "Default")
      (node (ref "IC12") (pin "9") (pinfunction "9_9") (pintype "passive"))
      (node (ref "IC16") (pin "11") (pinfunction "11_11") (pintype "passive"))
    )
    (net (code "23") (name "Net-(IC12-Pad14)") (class "Default")
      (node (ref "IC12") (pin "14") (pinfunction "14_14") (pintype "passive"))
      (node (ref "IC14") (pin "3") (pinfunction "3_3") (pintype "passive"))
    )
    (net (code "24") (name "Net-(IC13-Pad1)") (class "Default")
      (node (ref "IC13") (pin "1") (pinfunction "1_1") (pintype "passive"))
      (node (ref "IC5") (pin "14") (pinfunction "14_14") (pintype "passive"))
    )
    (net (code "25") (name "Net-(IC13-Pad3)") (class "Default")
      (node (ref "IC13") (pin "3") (pinfunction "3_3") (pintype "passive"))
      (node (ref "IC6") (pin "14") (pinfunction "14_14") (pintype "passive"))
    )
    (net (code "26") (name "Net-(IC13-Pad5)") (class "Default")
      (node (ref "IC13") (pin "5") (pinfunction "5_5") (pintype "passive"))
      (node (ref "IC7") (pin "14") (pinfunction "14_14") (pintype "passive"))
    )
    (net (code "27") (name "Net-(IC13-Pad9)") (class "Default")
      (node (ref "IC13") (pin "9") (pinfunction "9_9") (pintype "passive"))
      (node (ref "IC8") (pin "14") (pinfunction "14_14") (pintype "passive"))
    )
    (net (code "28") (name "Net-(IC13-Pad11)") (class "Default")
      (node (ref "IC13") (pin "11") (pinfunction "11_11") (pintype "passive"))
      (node (ref "IC9") (pin "14") (pinfunction "14_14") (pintype "passive"))
    )
    (net (code "29") (name "Net-(IC15-Pad3)") (class "Default")
      (node (ref "IC15") (pin "3") (pinfunction "3_3") (pintype "passive"))
      (node (ref "IC5") (pin "9") (pinfunction "9_9") (pintype "passive"))
    )
    (net (code "30") (name "Net-(IC15-Pad4)") (class "Default")
      (node (ref "IC15") (pin "4") (pinfunction "4_4") (pintype "passive"))
      (node (ref "IC6") (pin "9") (pinfunction "9_9") (pintype "passive"))
    )
    (net (code "31") (name "Net-(IC15-Pad8)") (class "Default")
      (node (ref "IC15") (pin "8") (pinfunction "8_8") (pintype "passive"))
      (node (ref "IC2") (pin "3") (pinfunction "3_3") (pintype "passive"))
      (node (ref "JP1") (pin "6") (pinfunction "6_6") (pintype "passive"))
    )
    (net (code "32") (name "Net-(IC15-Pad10)") (class "Default")
      (node (ref "IC15") (pin "10") (pinfunction "10_10") (pintype "passive"))
      (node (ref "IC7") (pin "9") (pinfunction "9_9") (pintype "passive"))
    )
    (net (code "33") (name "Net-(IC15-Pad11)") (class "Default")
      (node (ref "IC15") (pin "11") (pinfunction "11_11") (pintype "passive"))
      (node (ref "IC8") (pin "9") (pinfunction "9_9") (pintype "passive"))
    )
    (net (code "34") (name "Net-(IC15-Pad13)") (class "Default")
      (node (ref "IC15") (pin "13") (pinfunction "13_13") (pintype "passive"))
      (node (ref "IC2") (pin "11") (pinfunction "11_11") (pintype "passive"))
      (node (ref "JP1") (pin "5") (pinfunction "5_5") (pintype "passive"))
    )
    (net (code "35") (name "Net-(IC16-Pad1)") (class "Default")
      (node (ref "IC16") (pin "1") (pinfunction "1_1") (pintype "passive"))
      (node (ref "IC3") (pin "3") (pinfunction "3_3") (pintype "passive"))
      (node (ref "JP1") (pin "4") (pinfunction "4_4") (pintype "passive"))
    )
    (net (code "36") (name "Net-(IC16-Pad3)") (class "Default")
      (node (ref "IC16") (pin "3") (pinfunction "3_3") (pintype "passive"))
      (node (ref "IC9") (pin "9") (pinfunction "9_9") (pintype "passive"))
    )
    (net (code "37") (name "Net-(IC16-Pad6)") (class "Default")
      (node (ref "IC16") (pin "6") (pinfunction "6_6") (pintype "passive"))
      (node (ref "IC3") (pin "11") (pinfunction "11_11") (pintype "passive"))
      (node (ref "JP1") (pin "3") (pinfunction "3_3") (pintype "passive"))
    )
    (net (code "38") (name "Net-(IC16-Pad8)") (class "Default")
      (node (ref "IC16") (pin "8") (pinfunction "8_8") (pintype "passive"))
      (node (ref "IC4") (pin "3") (pinfunction "3_3") (pintype "passive"))
      (node (ref "JP1") (pin "2") (pinfunction "2_2") (pintype "passive"))
    )
    (net (code "39") (name "Net-(IC16-Pad13)") (class "Default")
      (node (ref "IC16") (pin "13") (pinfunction "13_13") (pintype "passive"))
      (node (ref "IC4") (pin "11") (pinfunction "11_11") (pintype "passive"))
      (node (ref "JP1") (pin "1") (pinfunction "1_1") (pintype "passive"))
    )
    (net (code "40") (name "Net-(Q1-B)") (class "Default")
      (node (ref "Q1") (pin "3") (pinfunction "B_3") (pintype "passive"))
      (node (ref "R3") (pin "1") (pinfunction "1_1") (pintype "passive"))
    )
    (net (code "41") (name "Net-(Q1-C)") (class "Default")
      (node (ref "D2") (pin "A") (pinfunction "A_A") (pintype "passive"))
      (node (ref "D3") (pin "A") (pinfunction "A_A") (pintype "passive"))
      (node (ref "Q1") (pin "2") (pinfunction "C_2") (pintype "passive"))
      (node (ref "X1") (pin "2") (pinfunction "S_2") (pintype "passive"))
    )
    (net (code "42") (name "Net-(Q2-B)") (class "Default")
      (node (ref "Q2") (pin "3") (pinfunction "B_3") (pintype "passive"))
      (node (ref "R6") (pin "1") (pinfunction "1_1") (pintype "passive"))
    )
    (net (code "43") (name "Net-(Q2-C)") (class "Default")
      (node (ref "D4") (pin "A") (pinfunction "A_A") (pintype "passive"))
      (node (ref "D5") (pin "A") (pinfunction "A_A") (pintype "passive"))
      (node (ref "Q2") (pin "2") (pinfunction "C_2") (pintype "passive"))
      (node (ref "X2") (pin "2") (pinfunction "S_2") (pintype "passive"))
    )
    (net (code "44") (name "Net-(Q3-B)") (class "Default")
      (node (ref "Q3") (pin "3") (pinfunction "B_3") (pintype "passive"))
      (node (ref "R9") (pin "1") (pinfunction "1_1") (pintype "passive"))
    )
    (net (code "45") (name "Net-(Q3-C)") (class "Default")
      (node (ref "D6") (pin "A") (pinfunction "A_A") (pintype "passive"))
      (node (ref "D7") (pin "A") (pinfunction "A_A") (pintype "passive"))
      (node (ref "Q3") (pin "2") (pinfunction "C_2") (pintype "passive"))
      (node (ref "X3") (pin "2") (pinfunction "S_2") (pintype "passive"))
    )
    (net (code "46") (name "Net-(Q4-B)") (class "Default")
      (node (ref "Q4") (pin "3") (pinfunction "B_3") (pintype "passive"))
      (node (ref "R12") (pin "1") (pinfunction "1_1") (pintype "passive"))
    )
    (net (code "47") (name "Net-(Q4-C)") (class "Default")
      (node (ref "D8") (pin "A") (pinfunction "A_A") (pintype "passive"))
      (node (ref "D9") (pin "A") (pinfunction "A_A") (pintype "passive"))
      (node (ref "Q4") (pin "2") (pinfunction "C_2") (pintype "passive"))
      (node (ref "X4") (pin "2") (pinfunction "S_2") (pintype "passive"))
    )
    (net (code "48") (name "Net-(Q5-B)") (class "Default")
      (node (ref "Q5") (pin "3") (pinfunction "B_3") (pintype "passive"))
      (node (ref "R15") (pin "1") (pinfunction "1_1") (pintype "passive"))
    )
    (net (code "49") (name "Net-(Q5-C)") (class "Default")
      (node (ref "D10") (pin "A") (pinfunction "A_A") (pintype "passive"))
      (node (ref "D11") (pin "A") (pinfunction "A_A") (pintype "passive"))
      (node (ref "Q5") (pin "2") (pinfunction "C_2") (pintype "passive"))
      (node (ref "X5") (pin "2") (pinfunction "S_2") (pintype "passive"))
    )
    (net (code "50") (name "Net-(Q6-B)") (class "Default")
      (node (ref "Q6") (pin "3") (pinfunction "B_3") (pintype "passive"))
      (node (ref "R18") (pin "1") (pinfunction "1_1") (pintype "passive"))
    )
    (net (code "51") (name "Net-(Q6-C)") (class "Default")
      (node (ref "D12") (pin "A") (pinfunction "A_A") (pintype "passive"))
      (node (ref "D13") (pin "A") (pinfunction "A_A") (pintype "passive"))
      (node (ref "Q6") (pin "2") (pinfunction "C_2") (pintype "passive"))
      (node (ref "X6") (pin "2") (pinfunction "S_2") (pintype "passive"))
    )
    (net (code "52") (name "Net-(Q7-B)") (class "Default")
      (node (ref "Q7") (pin "3") (pinfunction "B_3") (pintype "passive"))
      (node (ref "R21") (pin "1") (pinfunction "1_1") (pintype "passive"))
    )
    (net (code "53") (name "Net-(Q7-C)") (class "Default")
      (node (ref "D14") (pin "A") (pinfunction "A_A") (pintype "passive"))
      (node (ref "D15") (pin "A") (pinfunction "A_A") (pintype "passive"))
      (node (ref "Q7") (pin "2") (pinfunction "C_2") (pintype "passive"))
      (node (ref "X7") (pin "2") (pinfunction "S_2") (pintype "passive"))
    )
    (net (code "54") (name "Net-(Q8-B)") (class "Default")
      (node (ref "Q8") (pin "3") (pinfunction "B_3") (pintype "passive"))
      (node (ref "R24") (pin "1") (pinfunction "1_1") (pintype "passive"))
    )
    (net (code "55") (name "Net-(Q8-C)") (class "Default")
      (node (ref "D16") (pin "A") (pinfunction "A_A") (pintype "passive"))
      (node (ref "D17") (pin "A") (pinfunction "A_A") (pintype "passive"))
      (node (ref "Q8") (pin "2") (pinfunction "C_2") (pintype "passive"))
      (node (ref "X8") (pin "2") (pinfunction "S_2") (pintype "passive"))
    )
    (net (code "56") (name "Net-(U1-B)") (class "Default")
      (node (ref "R2") (pin "2") (pinfunction "2_2") (pintype "passive"))
      (node (ref "U1") (pin "2") (pinfunction "B_2") (pintype "passive"))
    )
    (net (code "57") (name "Net-(U1-C)") (class "Default")
      (node (ref "R3") (pin "2") (pinfunction "2_2") (pintype "passive"))
      (node (ref "U1") (pin "3") (pinfunction "C_3") (pintype "passive"))
    )
    (net (code "58") (name "Net-(U1-E)") (class "Default")
      (node (ref "IC13") (pin "2") (pinfunction "2_2") (pintype "passive"))
      (node (ref "IC5") (pin "3") (pinfunction "3_3") (pintype "passive"))
      (node (ref "U1") (pin "1") (pinfunction "E_1") (pintype "passive"))
    )
    (net (code "59") (name "Net-(U2-D)") (class "Default")
      (node (ref "D2") (pin "C") (pinfunction "C_C") (pintype "passive"))
      (node (ref "U2") (pin "2") (pinfunction "D_2") (pintype "passive"))
    )
    (net (code "60") (name "Net-(U2-G)") (class "Default")
      (node (ref "R4") (pin "2") (pinfunction "2_2") (pintype "passive"))
      (node (ref "U2") (pin "1") (pinfunction "G_1") (pintype "passive"))
    )
    (net (code "61") (name "Net-(U3-B)") (class "Default")
      (node (ref "R5") (pin "2") (pinfunction "2_2") (pintype "passive"))
      (node (ref "U3") (pin "2") (pinfunction "B_2") (pintype "passive"))
    )
    (net (code "62") (name "Net-(U3-C)") (class "Default")
      (node (ref "R6") (pin "2") (pinfunction "2_2") (pintype "passive"))
      (node (ref "U3") (pin "3") (pinfunction "C_3") (pintype "passive"))
    )
    (net (code "63") (name "Net-(U3-E)") (class "Default")
      (node (ref "IC13") (pin "4") (pinfunction "4_4") (pintype "passive"))
      (node (ref "IC6") (pin "3") (pinfunction "3_3") (pintype "passive"))
      (node (ref "U3") (pin "1") (pinfunction "E_1") (pintype "passive"))
    )
    (net (code "64") (name "Net-(U4-D)") (class "Default")
      (node (ref "D4") (pin "C") (pinfunction "C_C") (pintype "passive"))
      (node (ref "U4") (pin "2") (pinfunction "D_2") (pintype "passive"))
    )
    (net (code "65") (name "Net-(U4-G)") (class "Default")
      (node (ref "R7") (pin "2") (pinfunction "2_2") (pintype "passive"))
      (node (ref "U4") (pin "1") (pinfunction "G_1") (pintype "passive"))
    )
    (net (code "66") (name "Net-(U5-B)") (class "Default")
      (node (ref "R8") (pin "2") (pinfunction "2_2") (pintype "passive"))
      (node (ref "U5") (pin "2") (pinfunction "B_2") (pintype "passive"))
    )
    (net (code "67") (name "Net-(U5-C)") (class "Default")
      (node (ref "R9") (pin "2") (pinfunction "2_2") (pintype "passive"))
      (node (ref "U5") (pin "3") (pinfunction "C_3") (pintype "passive"))
    )
    (net (code "68") (name "Net-(U5-E)") (class "Default")
      (node (ref "IC13") (pin "6") (pinfunction "6_6") (pintype "passive"))
      (node (ref "IC7") (pin "3") (pinfunction "3_3") (pintype "passive"))
      (node (ref "U5") (pin "1") (pinfunction "E_1") (pintype "passive"))
    )
    (net (code "69") (name "Net-(U6-D)") (class "Default")
      (node (ref "D6") (pin "C") (pinfunction "C_C") (pintype "passive"))
      (node (ref "U6") (pin "2") (pinfunction "D_2") (pintype "passive"))
    )
    (net (code "70") (name "Net-(U6-G)") (class "Default")
      (node (ref "R10") (pin "2") (pinfunction "2_2") (pintype "passive"))
      (node (ref "U6") (pin "1") (pinfunction "G_1") (pintype "passive"))
    )
    (net (code "71") (name "Net-(U7-B)") (class "Default")
      (node (ref "R11") (pin "2") (pinfunction "2_2") (pintype "passive"))
      (node (ref "U7") (pin "2") (pinfunction "B_2") (pintype "passive"))
    )
    (net (code "72") (name "Net-(U7-C)") (class "Default")
      (node (ref "R12") (pin "2") (pinfunction "2_2") (pintype "passive"))
      (node (ref "U7") (pin "3") (pinfunction "C_3") (pintype "passive"))
    )
    (net (code "73") (name "Net-(U7-E)") (class "Default")
      (node (ref "IC13") (pin "8") (pinfunction "8_8") (pintype "passive"))
      (node (ref "IC8") (pin "3") (pinfunction "3_3") (pintype "passive"))
      (node (ref "U7") (pin "1") (pinfunction "E_1") (pintype "passive"))
    )
    (net (code "74") (name "Net-(U8-D)") (class "Default")
      (node (ref "D8") (pin "C") (pinfunction "C_C") (pintype "passive"))
      (node (ref "U8") (pin "2") (pinfunction "D_2") (pintype "passive"))
    )
    (net (code "75") (name "Net-(U8-G)") (class "Default")
      (node (ref "R13") (pin "2") (pinfunction "2_2") (pintype "passive"))
      (node (ref "U8") (pin "1") (pinfunction "G_1") (pintype "passive"))
    )
    (net (code "76") (name "Net-(U9-B)") (class "Default")
      (node (ref "R14") (pin "2") (pinfunction "2_2") (pintype "passive"))
      (node (ref "U9") (pin "2") (pinfunction "B_2") (pintype "passive"))
    )
    (net (code "77") (name "Net-(U9-C)") (class "Default")
      (node (ref "R15") (pin "2") (pinfunction "2_2") (pintype "passive"))
      (node (ref "U9") (pin "3") (pinfunction "C_3") (pintype "passive"))
    )
    (net (code "78") (name "Net-(U9-E)") (class "Default")
      (node (ref "IC13") (pin "10") (pinfunction "10_10") (pintype "passive"))
      (node (ref "IC9") (pin "3") (pinfunction "3_3") (pintype "passive"))
      (node (ref "U9") (pin "1") (pinfunction "E_1") (pintype "passive"))
    )
    (net (code "79") (name "Net-(U10-D)") (class "Default")
      (node (ref "D10") (pin "C") (pinfunction "C_C") (pintype "passive"))
      (node (ref "U10") (pin "2") (pinfunction "D_2") (pintype "passive"))
    )
    (net (code "80") (name "Net-(U10-G)") (class "Default")
      (node (ref "R16") (pin "2") (pinfunction "2_2") (pintype "passive"))
      (node (ref "U10") (pin "1") (pinfunction "G_1") (pintype "passive"))
    )
    (net (code "81") (name "Net-(U11-B)") (class "Default")
      (node (ref "R17") (pin "2") (pinfunction "2_2") (pintype "passive"))
      (node (ref "U11") (pin "2") (pinfunction "B_2") (pintype "passive"))
    )
    (net (code "82") (name "Net-(U11-C)") (class "Default")
      (node (ref "R18") (pin "2") (pinfunction "2_2") (pintype "passive"))
      (node (ref "U11") (pin "3") (pinfunction "C_3") (pintype "passive"))
    )
    (net (code "83") (name "Net-(U11-E)") (class "Default")
      (node (ref "IC10") (pin "3") (pinfunction "3_3") (pintype "passive"))
      (node (ref "IC13") (pin "12") (pinfunction "12_12") (pintype "passive"))
      (node (ref "U11") (pin "1") (pinfunction "E_1") (pintype "passive"))
    )
    (net (code "84") (name "Net-(U12-D)") (class "Default")
      (node (ref "D12") (pin "C") (pinfunction "C_C") (pintype "passive"))
      (node (ref "U12") (pin "2") (pinfunction "D_2") (pintype "passive"))
    )
    (net (code "85") (name "Net-(U12-G)") (class "Default")
      (node (ref "R19") (pin "2") (pinfunction "2_2") (pintype "passive"))
      (node (ref "U12") (pin "1") (pinfunction "G_1") (pintype "passive"))
    )
    (net (code "86") (name "Net-(U13-B)") (class "Default")
      (node (ref "R20") (pin "2") (pinfunction "2_2") (pintype "passive"))
      (node (ref "U13") (pin "2") (pinfunction "B_2") (pintype "passive"))
    )
    (net (code "87") (name "Net-(U13-C)") (class "Default")
      (node (ref "R21") (pin "2") (pinfunction "2_2") (pintype "passive"))
      (node (ref "U13") (pin "3") (pinfunction "C_3") (pintype "passive"))
    )
    (net (code "88") (name "Net-(U13-E)") (class "Default")
      (node (ref "IC11") (pin "3") (pinfunction "3_3") (pintype "passive"))
      (node (ref "IC14") (pin "2") (pinfunction "2_2") (pintype "passive"))
      (node (ref "U13") (pin "1") (pinfunction "E_1") (pintype "passive"))
    )
    (net (code "89") (name "Net-(U14-D)") (class "Default")
      (node (ref "D14") (pin "C") (pinfunction "C_C") (pintype "passive"))
      (node (ref "U14") (pin "2") (pinfunction "D_2") (pintype "passive"))
    )
    (net (code "90") (name "Net-(U14-G)") (class "Default")
      (node (ref "R22") (pin "2") (pinfunction "2_2") (pintype "passive"))
      (node (ref "U14") (pin "1") (pinfunction "G_1") (pintype "passive"))
    )
    (net (code "91") (name "Net-(U15-B)") (class "Default")
      (node (ref "R23") (pin "2") (pinfunction "2_2") (pintype "passive"))
      (node (ref "U15") (pin "2") (pinfunction "B_2") (pintype "passive"))
    )
    (net (code "92") (name "Net-(U15-C)") (class "Default")
      (node (ref "R24") (pin "2") (pinfunction "2_2") (pintype "passive"))
      (node (ref "U15") (pin "3") (pinfunction "C_3") (pintype "passive"))
    )
    (net (code "93") (name "Net-(U15-E)") (class "Default")
      (node (ref "IC12") (pin "3") (pinfunction "3_3") (pintype "passive"))
      (node (ref "IC14") (pin "4") (pinfunction "4_4") (pintype "passive"))
      (node (ref "U15") (pin "1") (pinfunction "E_1") (pintype "passive"))
    )
    (net (code "94") (name "Net-(U16-D)") (class "Default")
      (node (ref "D16") (pin "C") (pinfunction "C_C") (pintype "passive"))
      (node (ref "U16") (pin "2") (pinfunction "D_2") (pintype "passive"))
    )
    (net (code "95") (name "Net-(U16-G)") (class "Default")
      (node (ref "R25") (pin "2") (pinfunction "2_2") (pintype "passive"))
      (node (ref "U16") (pin "1") (pinfunction "G_1") (pintype "passive"))
    )
    (net (code "96") (name "RESET") (class "Default")
      (node (ref "IC1") (pin "10") (pinfunction "10_10") (pintype "passive"))
      (node (ref "IC1") (pin "4") (pinfunction "4_4") (pintype "passive"))
      (node (ref "IC14") (pin "12") (pinfunction "12_12") (pintype "passive"))
      (node (ref "IC2") (pin "10") (pinfunction "10_10") (pintype "passive"))
      (node (ref "IC2") (pin "4") (pinfunction "4_4") (pintype "passive"))
      (node (ref "IC3") (pin "10") (pinfunction "10_10") (pintype "passive"))
      (node (ref "IC3") (pin "4") (pinfunction "4_4") (pintype "passive"))
      (node (ref "IC4") (pin "10") (pinfunction "10_10") (pintype "passive"))
      (node (ref "IC4") (pin "4") (pinfunction "4_4") (pintype "passive"))
    )
    (net (code "97") (name "STATE") (class "Default")
      (node (ref "IC1") (pin "5") (pinfunction "5_5") (pintype "passive"))
      (node (ref "IC1") (pin "9") (pinfunction "9_9") (pintype "passive"))
      (node (ref "IC14") (pin "5") (pinfunction "5_5") (pintype "passive"))
      (node (ref "IC2") (pin "5") (pinfunction "5_5") (pintype "passive"))
      (node (ref "IC2") (pin "9") (pinfunction "9_9") (pintype "passive"))
      (node (ref "IC3") (pin "5") (pinfunction "5_5") (pintype "passive"))
      (node (ref "IC3") (pin "9") (pinfunction "9_9") (pintype "passive"))
      (node (ref "IC4") (pin "5") (pinfunction "5_5") (pintype "passive"))
      (node (ref "IC4") (pin "9") (pinfunction "9_9") (pintype "passive"))
      (node (ref "X16") (pin "1") (pinfunction "S_1") (pintype "passive"))
    )
    (net (code "98") (name "V0") (class "Default")
      (node (ref "IC10") (pin "4") (pinfunction "4_4") (pintype "passive"))
      (node (ref "IC11") (pin "4") (pinfunction "4_4") (pintype "passive"))
      (node (ref "IC12") (pin "4") (pinfunction "4_4") (pintype "passive"))
      (node (ref "IC5") (pin "4") (pinfunction "4_4") (pintype "passive"))
      (node (ref "IC6") (pin "4") (pinfunction "4_4") (pintype "passive"))
      (node (ref "IC7") (pin "4") (pinfunction "4_4") (pintype "passive"))
      (node (ref "IC8") (pin "4") (pinfunction "4_4") (pintype "passive"))
      (node (ref "IC9") (pin "4") (pinfunction "4_4") (pintype "passive"))
      (node (ref "JP2") (pin "1") (pinfunction "1_1") (pintype "passive"))
    )
    (net (code "99") (name "V1") (class "Default")
      (node (ref "IC10") (pin "5") (pinfunction "5_5") (pintype "passive"))
      (node (ref "IC11") (pin "5") (pinfunction "5_5") (pintype "passive"))
      (node (ref "IC12") (pin "5") (pinfunction "5_5") (pintype "passive"))
      (node (ref "IC5") (pin "5") (pinfunction "5_5") (pintype "passive"))
      (node (ref "IC6") (pin "5") (pinfunction "5_5") (pintype "passive"))
      (node (ref "IC7") (pin "5") (pinfunction "5_5") (pintype "passive"))
      (node (ref "IC8") (pin "5") (pinfunction "5_5") (pintype "passive"))
      (node (ref "IC9") (pin "5") (pinfunction "5_5") (pintype "passive"))
      (node (ref "JP2") (pin "2") (pinfunction "2_2") (pintype "passive"))
    )
    (net (code "100") (name "V2") (class "Default")
      (node (ref "IC10") (pin "6") (pinfunction "6_6") (pintype "passive"))
      (node (ref "IC11") (pin "6") (pinfunction "6_6") (pintype "passive"))
      (node (ref "IC12") (pin "6") (pinfunction "6_6") (pintype "passive"))
      (node (ref "IC5") (pin "6") (pinfunction "6_6") (pintype "passive"))
      (node (ref "IC6") (pin "6") (pinfunction "6_6") (pintype "passive"))
      (node (ref "IC7") (pin "6") (pinfunction "6_6") (pintype "passive"))
      (node (ref "IC8") (pin "6") (pinfunction "6_6") (pintype "passive"))
      (node (ref "IC9") (pin "6") (pinfunction "6_6") (pintype "passive"))
      (node (ref "JP2") (pin "3") (pinfunction "3_3") (pintype "passive"))
    )
    (net (code "101") (name "V3") (class "Default")
      (node (ref "IC10") (pin "7") (pinfunction "7_7") (pintype "passive"))
      (node (ref "IC11") (pin "7") (pinfunction "7_7") (pintype "passive"))
      (node (ref "IC12") (pin "7") (pinfunction "7_7") (pintype "passive"))
      (node (ref "IC5") (pin "7") (pinfunction "7_7") (pintype "passive"))
      (node (ref "IC6") (pin "7") (pinfunction "7_7") (pintype "passive"))
      (node (ref "IC7") (pin "7") (pinfunction "7_7") (pintype "passive"))
      (node (ref "IC8") (pin "7") (pinfunction "7_7") (pintype "passive"))
      (node (ref "IC9") (pin "7") (pinfunction "7_7") (pintype "passive"))
      (node (ref "JP2") (pin "4") (pinfunction "4_4") (pintype "passive"))
    )
    (net (code "102") (name "V4") (class "Default")
      (node (ref "IC10") (pin "10") (pinfunction "10_10") (pintype "passive"))
      (node (ref "IC11") (pin "10") (pinfunction "10_10") (pintype "passive"))
      (node (ref "IC12") (pin "10") (pinfunction "10_10") (pintype "passive"))
      (node (ref "IC5") (pin "10") (pinfunction "10_10") (pintype "passive"))
      (node (ref "IC6") (pin "10") (pinfunction "10_10") (pintype "passive"))
      (node (ref "IC7") (pin "10") (pinfunction "10_10") (pintype "passive"))
      (node (ref "IC8") (pin "10") (pinfunction "10_10") (pintype "passive"))
      (node (ref "IC9") (pin "10") (pinfunction "10_10") (pintype "passive"))
      (node (ref "JP2") (pin "5") (pinfunction "5_5") (pintype "passive"))
    )
    (net (code "103") (name "V5") (class "Default")
      (node (ref "IC10") (pin "11") (pinfunction "11_11") (pintype "passive"))
      (node (ref "IC11") (pin "11") (pinfunction "11_11") (pintype "passive"))
      (node (ref "IC12") (pin "11") (pinfunction "11_11") (pintype "passive"))
      (node (ref "IC5") (pin "11") (pinfunction "11_11") (pintype "passive"))
      (node (ref "IC6") (pin "11") (pinfunction "11_11") (pintype "passive"))
      (node (ref "IC7") (pin "11") (pinfunction "11_11") (pintype "passive"))
      (node (ref "IC8") (pin "11") (pinfunction "11_11") (pintype "passive"))
      (node (ref "IC9") (pin "11") (pinfunction "11_11") (pintype "passive"))
      (node (ref "JP2") (pin "6") (pinfunction "6_6") (pintype "passive"))
    )
    (net (code "104") (name "V6") (class "Default")
      (node (ref "IC10") (pin "12") (pinfunction "12_12") (pintype "passive"))
      (node (ref "IC11") (pin "12") (pinfunction "12_12") (pintype "passive"))
      (node (ref "IC12") (pin "12") (pinfunction "12_12") (pintype "passive"))
      (node (ref "IC5") (pin "12") (pinfunction "12_12") (pintype "passive"))
      (node (ref "IC6") (pin "12") (pinfunction "12_12") (pintype "passive"))
      (node (ref "IC7") (pin "12") (pinfunction "12_12") (pintype "passive"))
      (node (ref "IC8") (pin "12") (pinfunction "12_12") (pintype "passive"))
      (node (ref "IC9") (pin "12") (pinfunction "12_12") (pintype "passive"))
      (node (ref "JP2") (pin "7") (pinfunction "7_7") (pintype "passive"))
    )
    (net (code "105") (name "V7") (class "Default")
      (node (ref "IC10") (pin "13") (pinfunction "13_13") (pintype "passive"))
      (node (ref "IC11") (pin "13") (pinfunction "13_13") (pintype "passive"))
      (node (ref "IC12") (pin "13") (pinfunction "13_13") (pintype "passive"))
      (node (ref "IC5") (pin "13") (pinfunction "13_13") (pintype "passive"))
      (node (ref "IC6") (pin "13") (pinfunction "13_13") (pintype "passive"))
      (node (ref "IC7") (pin "13") (pinfunction "13_13") (pintype "passive"))
      (node (ref "IC8") (pin "13") (pinfunction "13_13") (pintype "passive"))
      (node (ref "IC9") (pin "13") (pinfunction "13_13") (pintype "passive"))
      (node (ref "JP2") (pin "8") (pinfunction "8_8") (pintype "passive"))
    )
    (net (code "106") (name "unconnected-(IC1-Pad2)") (class "Default")
      (node (ref "IC1") (pin "2") (pinfunction "2_2") (pintype "passive"))
    )
    (net (code "107") (name "unconnected-(IC1-Pad12)") (class "Default")
      (node (ref "IC1") (pin "12") (pinfunction "12_12") (pintype "passive"))
    )
    (net (code "108") (name "unconnected-(IC2-Pad2)") (class "Default")
      (node (ref "IC2") (pin "2") (pinfunction "2_2") (pintype "passive"))
    )
    (net (code "109") (name "unconnected-(IC2-Pad12)") (class "Default")
      (node (ref "IC2") (pin "12") (pinfunction "12_12") (pintype "passive"))
    )
    (net (code "110") (name "unconnected-(IC3-Pad2)") (class "Default")
      (node (ref "IC3") (pin "2") (pinfunction "2_2") (pintype "passive"))
    )
    (net (code "111") (name "unconnected-(IC3-Pad6)") (class "Default")
      (node (ref "IC3") (pin "6") (pinfunction "6_6") (pintype "passive"))
    )
    (net (code "112") (name "unconnected-(IC3-Pad8)") (class "Default")
      (node (ref "IC3") (pin "8") (pinfunction "8_8") (pintype "passive"))
    )
    (net (code "113") (name "unconnected-(IC3-Pad12)") (class "Default")
      (node (ref "IC3") (pin "12") (pinfunction "12_12") (pintype "passive"))
    )
    (net (code "114") (name "unconnected-(IC4-Pad2)") (class "Default")
      (node (ref "IC4") (pin "2") (pinfunction "2_2") (pintype "passive"))
    )
    (net (code "115") (name "unconnected-(IC4-Pad6)") (class "Default")
      (node (ref "IC4") (pin "6") (pinfunction "6_6") (pintype "passive"))
    )
    (net (code "116") (name "unconnected-(IC4-Pad8)") (class "Default")
      (node (ref "IC4") (pin "8") (pinfunction "8_8") (pintype "passive"))
    )
    (net (code "117") (name "unconnected-(IC4-Pad12)") (class "Default")
      (node (ref "IC4") (pin "12") (pinfunction "12_12") (pintype "passive"))
    )
    (net (code "118") (name "unconnected-(IC6-Pad15)") (class "Default")
      (node (ref "IC6") (pin "15") (pinfunction "15_15") (pintype "passive"))
    )
    (net (code "119") (name "unconnected-(IC14-Pad8)") (class "Default")
      (node (ref "IC14") (pin "8") (pinfunction "8_8") (pintype "passive"))
    )
    (net (code "120") (name "unconnected-(IC14-Pad10)") (class "Default")
      (node (ref "IC14") (pin "10") (pinfunction "10_10") (pintype "passive"))
    )
  )
)
